# Grove_-_LoRa_Radio_433MHz_v1_0.net
KiCad netlist of a schematic drawn in EAGLE
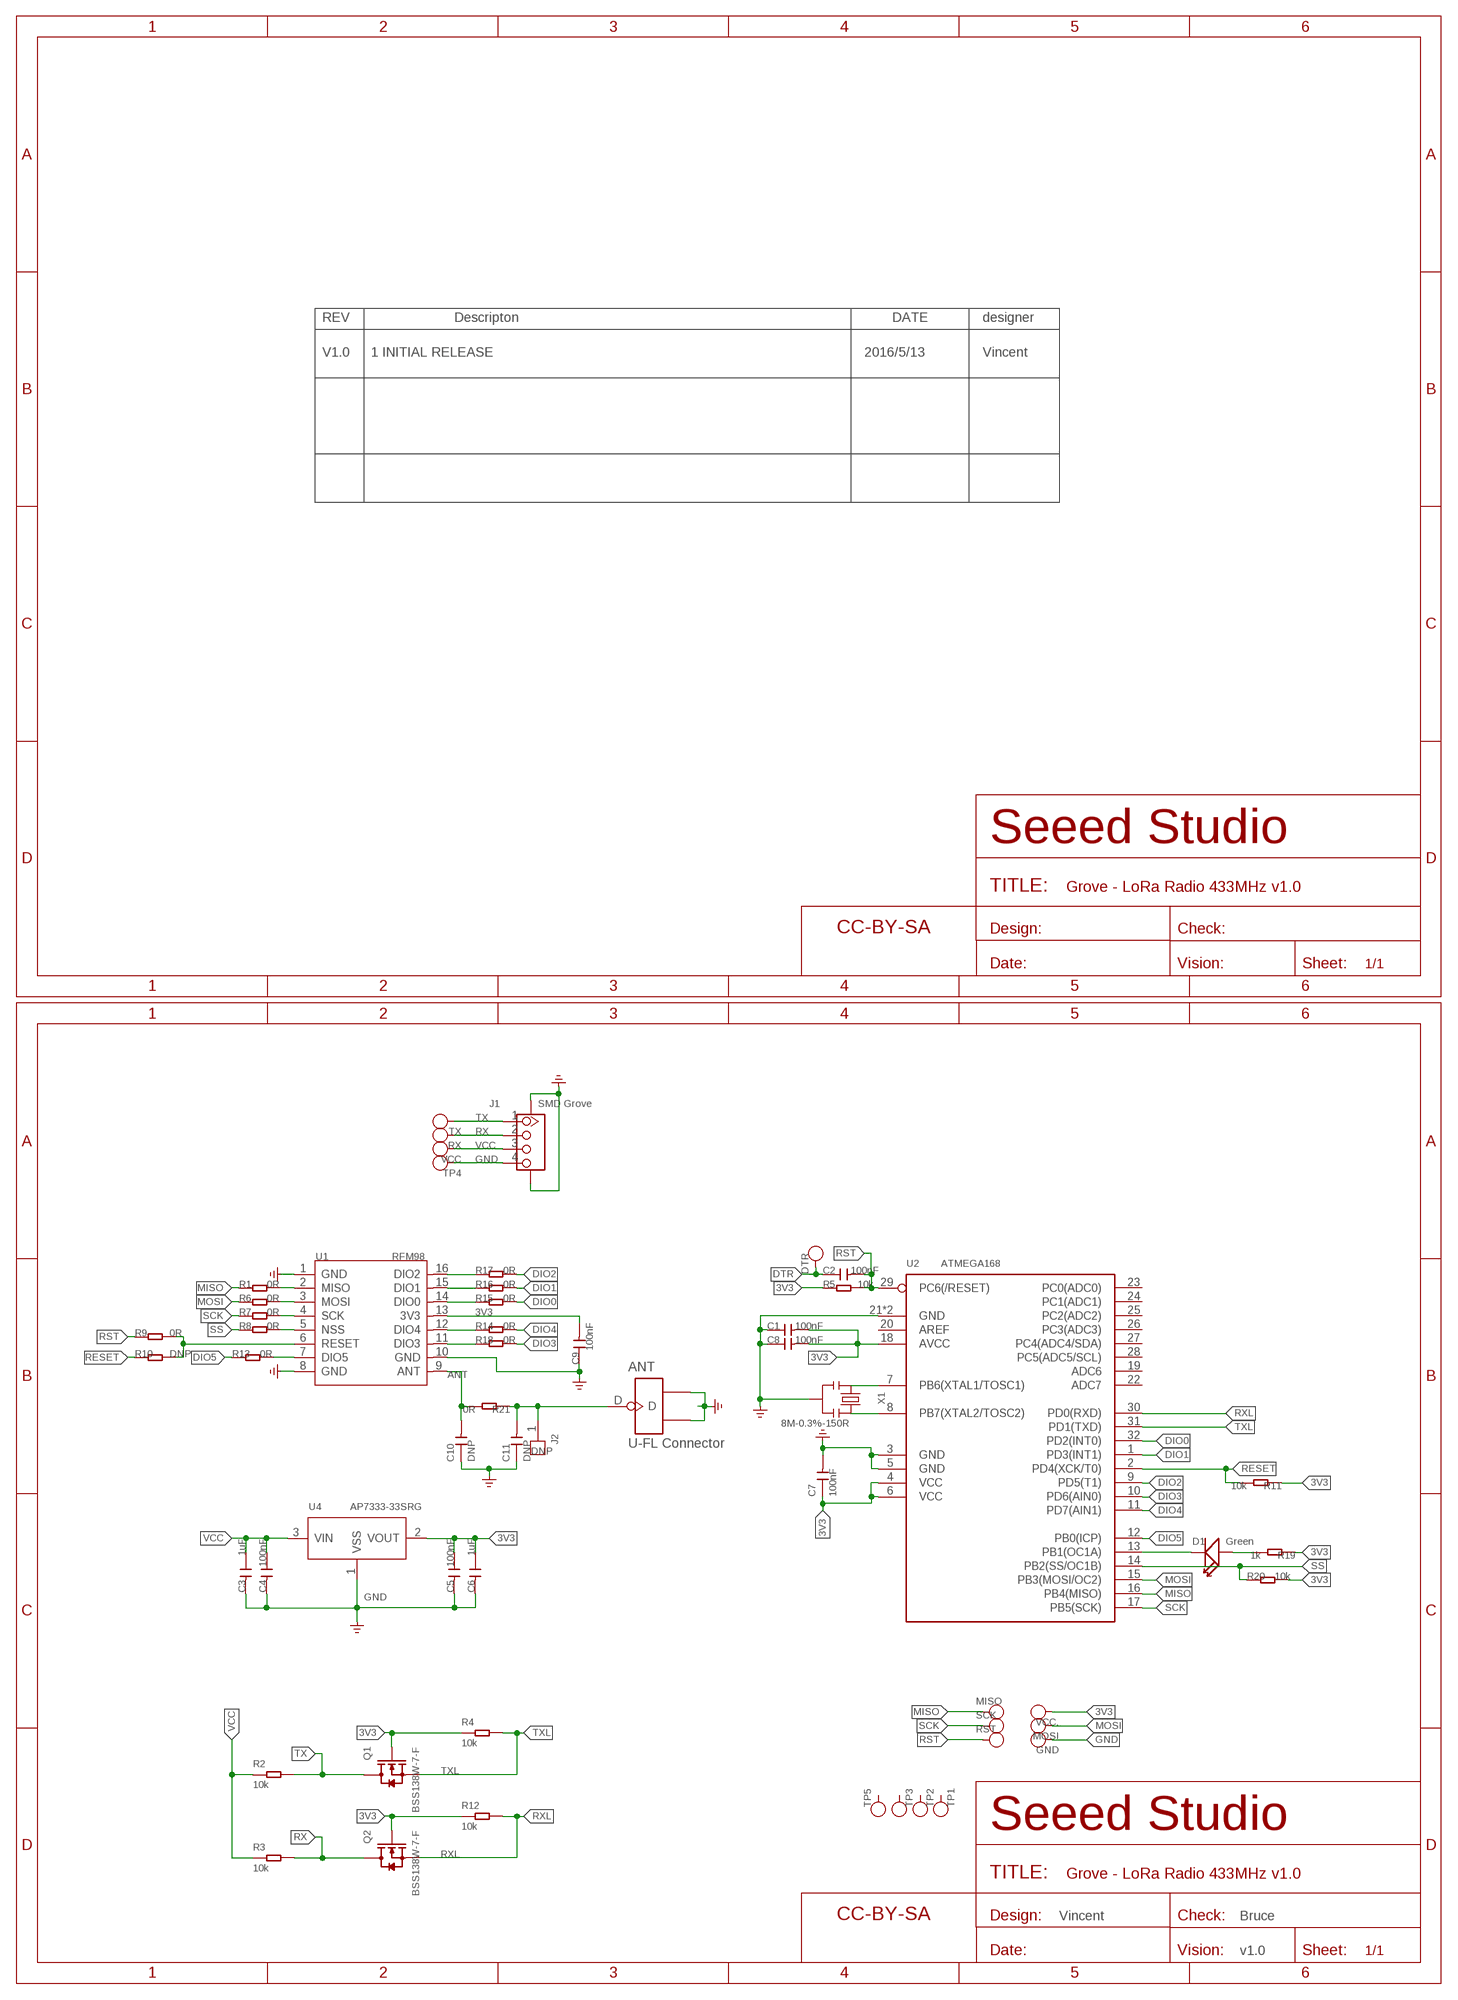
[diagram p0: schematic, sheet 1]

(export (version "E")
  (design (tool "Eeschema 10.0.6"))
  (components
    (comp (ref "ANT")
      (value "U-FL Connector")
      (footprint "eagle-import:U-FL3P-SMD-2.6X2.6X1.0MM")
      (libsource (lib "eagle-import") (part "ANTENNA-U-FL"))
    )
    (comp (ref "C1")
      (value "100nF")
      (footprint "eagle-import:C0402")
      (libsource (lib "eagle-import") (part "CAP-0402"))
    )
    (comp (ref "C2")
      (value "100nF")
      (footprint "eagle-import:C0402")
      (libsource (lib "eagle-import") (part "CAP-0402"))
    )
    (comp (ref "C3")
      (value "1uF")
      (footprint "eagle-import:C0402")
      (libsource (lib "eagle-import") (part "CAP-0402"))
    )
    (comp (ref "C4")
      (value "100nF")
      (footprint "eagle-import:C0402")
      (libsource (lib "eagle-import") (part "CAP-0402"))
    )
    (comp (ref "C5")
      (value "100nF")
      (footprint "eagle-import:C0402")
      (libsource (lib "eagle-import") (part "CAP-0402"))
    )
    (comp (ref "C6")
      (value "1uF")
      (footprint "eagle-import:C0402")
      (libsource (lib "eagle-import") (part "CAP-0402"))
    )
    (comp (ref "C7")
      (value "100nF")
      (footprint "eagle-import:C0402")
      (libsource (lib "eagle-import") (part "CAP-0402"))
    )
    (comp (ref "C8")
      (value "100nF")
      (footprint "eagle-import:C0402")
      (libsource (lib "eagle-import") (part "CAP-0402"))
    )
    (comp (ref "C9")
      (value "100nF")
      (footprint "eagle-import:C0402")
      (libsource (lib "eagle-import") (part "CAP-0402"))
    )
    (comp (ref "C10")
      (value "DNP")
      (footprint "eagle-import:C0402")
      (libsource (lib "eagle-import") (part "CAP-0402"))
    )
    (comp (ref "C11")
      (value "DNP")
      (footprint "eagle-import:C0402")
      (libsource (lib "eagle-import") (part "CAP-0402"))
    )
    (comp (ref "D1")
      (value "Green")
      (footprint "eagle-import:LED-0402")
      (libsource (lib "eagle-import") (part "LED-0402"))
    )
    (comp (ref "DTR")
      (value "TEST-POINT'4545'")
      (footprint "eagle-import:TP-D45MIL")
      (fields (field (name "PARTNO") "DNP"))
      (libsource (lib "eagle-import") (part "TEST-POINT'4545'"))
    )
    (comp (ref "FR1")
      (value "SEEEDSTUDIO-OPEN-SCH-FRAME")
      (footprint "eagle-import:SEEEDSTUDIO-PCB-FRAME")
      (libsource (lib "eagle-import") (part "SEEEDSTUDIO-OPEN-SCH-FRAME"))
    )
    (comp (ref "FR2")
      (value "SEEEDSTUDIO-OPEN-SCH-FRAME")
      (footprint "eagle-import:SEEEDSTUDIO-PCB-FRAME")
      (libsource (lib "eagle-import") (part "SEEEDSTUDIO-OPEN-SCH-FRAME"))
    )
    (comp (ref "GND")
      (value "DNP")
      (footprint "eagle-import:TP-D45MIL")
      (libsource (lib "eagle-import") (part "PAD-TEST-POINT'4545'"))
    )
    (comp (ref "J1")
      (value "SMD Grove")
      (footprint "eagle-import:HW4-SMD-2.0")
      (libsource (lib "eagle-import") (part "GROVE-CONNECTOR-SMD'DD'"))
    )
    (comp (ref "J2")
      (value "DNP")
      (footprint "eagle-import:1P-65_35MIL")
      (libsource (lib "eagle-import") (part "HEADER-1P-35"))
    )
    (comp (ref "MISO")
      (value "DNP")
      (footprint "eagle-import:TP-D45MIL")
      (libsource (lib "eagle-import") (part "PAD-TEST-POINT'4545'"))
    )
    (comp (ref "MOSI")
      (value "DNP")
      (footprint "eagle-import:TP-D45MIL")
      (libsource (lib "eagle-import") (part "PAD-TEST-POINT'4545'"))
    )
    (comp (ref "Q1")
      (value "BSS138W-7-F")
      (footprint "eagle-import:SOT-323")
      (libsource (lib "eagle-import") (part "MOSFET-N'SI1304BDL'"))
    )
    (comp (ref "Q2")
      (value "BSS138W-7-F")
      (footprint "eagle-import:SOT-323")
      (libsource (lib "eagle-import") (part "MOSFET-N'SI1304BDL'"))
    )
    (comp (ref "R1")
      (value "0R")
      (footprint "eagle-import:R0402")
      (libsource (lib "eagle-import") (part "RES-0402"))
    )
    (comp (ref "R2")
      (value "10k")
      (footprint "eagle-import:R0402")
      (libsource (lib "eagle-import") (part "RES-0402"))
    )
    (comp (ref "R3")
      (value "10k")
      (footprint "eagle-import:R0402")
      (libsource (lib "eagle-import") (part "RES-0402"))
    )
    (comp (ref "R4")
      (value "10k")
      (footprint "eagle-import:R0402")
      (libsource (lib "eagle-import") (part "RES-0402"))
    )
    (comp (ref "R5")
      (value "10k")
      (footprint "eagle-import:R0402")
      (libsource (lib "eagle-import") (part "RES-0402"))
    )
    (comp (ref "R6")
      (value "0R")
      (footprint "eagle-import:R0402")
      (libsource (lib "eagle-import") (part "RES-0402"))
    )
    (comp (ref "R7")
      (value "0R")
      (footprint "eagle-import:R0402")
      (libsource (lib "eagle-import") (part "RES-0402"))
    )
    (comp (ref "R8")
      (value "0R")
      (footprint "eagle-import:R0402")
      (libsource (lib "eagle-import") (part "RES-0402"))
    )
    (comp (ref "R9")
      (value "0R")
      (footprint "eagle-import:R0402")
      (libsource (lib "eagle-import") (part "RES-0402"))
    )
    (comp (ref "R10")
      (value "DNP")
      (footprint "eagle-import:R0402")
      (libsource (lib "eagle-import") (part "RES-0402"))
    )
    (comp (ref "R11")
      (value "10k")
      (footprint "eagle-import:R0402")
      (libsource (lib "eagle-import") (part "RES-0402"))
    )
    (comp (ref "R12")
      (value "10k")
      (footprint "eagle-import:R0402")
      (libsource (lib "eagle-import") (part "RES-0402"))
    )
    (comp (ref "R13")
      (value "0R")
      (footprint "eagle-import:R0402")
      (libsource (lib "eagle-import") (part "RES-0402"))
    )
    (comp (ref "R14")
      (value "0R")
      (footprint "eagle-import:R0402")
      (libsource (lib "eagle-import") (part "RES-0402"))
    )
    (comp (ref "R15")
      (value "0R")
      (footprint "eagle-import:R0402")
      (libsource (lib "eagle-import") (part "RES-0402"))
    )
    (comp (ref "R16")
      (value "0R")
      (footprint "eagle-import:R0402")
      (libsource (lib "eagle-import") (part "RES-0402"))
    )
    (comp (ref "R17")
      (value "0R")
      (footprint "eagle-import:R0402")
      (libsource (lib "eagle-import") (part "RES-0402"))
    )
    (comp (ref "R18")
      (value "0R")
      (footprint "eagle-import:R0402")
      (libsource (lib "eagle-import") (part "RES-0402"))
    )
    (comp (ref "R19")
      (value "1k")
      (footprint "eagle-import:R0402")
      (libsource (lib "eagle-import") (part "RES-0402"))
    )
    (comp (ref "R20")
      (value "10k")
      (footprint "eagle-import:R0402")
      (libsource (lib "eagle-import") (part "RES-0402"))
    )
    (comp (ref "R21")
      (value "0R")
      (footprint "eagle-import:R0603")
      (libsource (lib "eagle-import") (part "R-0603"))
    )
    (comp (ref "RST")
      (value "DNP")
      (footprint "eagle-import:TP-D45MIL")
      (libsource (lib "eagle-import") (part "PAD-TEST-POINT'4545'"))
    )
    (comp (ref "RX")
      (value "TEST-POINT'4545'")
      (footprint "eagle-import:TP-D45MIL")
      (fields (field (name "PARTNO") "DNP"))
      (libsource (lib "eagle-import") (part "TEST-POINT'4545'"))
    )
    (comp (ref "SCK")
      (value "DNP")
      (footprint "eagle-import:TP-D45MIL")
      (libsource (lib "eagle-import") (part "PAD-TEST-POINT'4545'"))
    )
    (comp (ref "TP1")
      (value "TEST-POINT'4545'")
      (footprint "eagle-import:TP-D45MIL")
      (fields (field (name "PARTNO") "DNP"))
      (libsource (lib "eagle-import") (part "TEST-POINT'4545'"))
    )
    (comp (ref "TP2")
      (value "TEST-POINT'4545'")
      (footprint "eagle-import:TP-D45MIL")
      (fields (field (name "PARTNO") "DNP"))
      (libsource (lib "eagle-import") (part "TEST-POINT'4545'"))
    )
    (comp (ref "TP3")
      (value "TEST-POINT'4545'")
      (footprint "eagle-import:TP-D45MIL")
      (fields (field (name "PARTNO") "DNP"))
      (libsource (lib "eagle-import") (part "TEST-POINT'4545'"))
    )
    (comp (ref "TP4")
      (value "TEST-POINT'4545'")
      (footprint "eagle-import:TP-D45MIL")
      (fields (field (name "PARTNO") "DNP"))
      (libsource (lib "eagle-import") (part "TEST-POINT'4545'"))
    )
    (comp (ref "TP5")
      (value "TEST-POINT'4545'")
      (footprint "eagle-import:TP-D45MIL")
      (fields (field (name "PARTNO") "DNP"))
      (libsource (lib "eagle-import") (part "TEST-POINT'4545'"))
    )
    (comp (ref "TX")
      (value "TEST-POINT'4545'")
      (footprint "eagle-import:TP-D45MIL")
      (fields (field (name "PARTNO") "DNP"))
      (libsource (lib "eagle-import") (part "TEST-POINT'4545'"))
    )
    (comp (ref "U1")
      (value "RFM98")
      (footprint "eagle-import:MODEM16-2-16X16X1.8MM")
      (libsource (lib "eagle-import") (part "MOUDLE-MODEM-RFM95/96/97/98"))
    )
    (comp (ref "U2")
      (value "ATMEGA168")
      (footprint "eagle-import:QFN32G-0.5-5X5MM")
      (libsource (lib "eagle-import") (part "MCU-ATMEGA8/168/328MU"))
    )
    (comp (ref "U4")
      (value "AP7333-33SRG")
      (footprint "eagle-import:SOT-23")
      (libsource (lib "eagle-import") (part "PMIC-XC6206PMR"))
    )
    (comp (ref "VCC")
      (value "TEST-POINT'4545'")
      (footprint "eagle-import:TP-D45MIL")
      (fields (field (name "PARTNO") "DNP"))
      (libsource (lib "eagle-import") (part "TEST-POINT'4545'"))
    )
    (comp (ref "VCC.")
      (value "NC")
      (footprint "eagle-import:TP-D45MIL")
      (fields (field (name "PARTNO") "DNP"))
      (libsource (lib "eagle-import") (part "PAD-TEST-POINT'4545'"))
    )
    (comp (ref "X1")
      (value "8M-0.3%-150R")
      (footprint "eagle-import:RESONATOR3-SMD-3.6X1.3X0.8MM")
      (libsource (lib "eagle-import") (part "CRYSTAL-RESONATOR'SMD'"))
    )
  )
  (nets
    (net (code "1") (name "/ANT") (class "Default")
      (node (ref "C10") (pin "2") (pinfunction "2_2") (pintype "passive"))
      (node (ref "R21") (pin "2") (pinfunction "2_2") (pintype "passive"))
      (node (ref "U1") (pin "9") (pinfunction "ANT_9") (pintype "bidirectional"))
    )
    (net (code "2") (name "3V3") (class "Default")
      (node (ref "C1") (pin "2") (pinfunction "2_2") (pintype "passive"))
      (node (ref "C5") (pin "1") (pinfunction "1_1") (pintype "passive"))
      (node (ref "C6") (pin "1") (pinfunction "1_1") (pintype "passive"))
      (node (ref "C7") (pin "1") (pinfunction "1_1") (pintype "passive"))
      (node (ref "C8") (pin "2") (pinfunction "2_2") (pintype "passive"))
      (node (ref "C9") (pin "2") (pinfunction "2_2") (pintype "passive"))
      (node (ref "Q1") (pin "1") (pinfunction "G_1") (pintype "passive"))
      (node (ref "Q2") (pin "1") (pinfunction "G_1") (pintype "passive"))
      (node (ref "R11") (pin "2") (pinfunction "2_2") (pintype "passive"))
      (node (ref "R12") (pin "1") (pinfunction "1_1") (pintype "passive"))
      (node (ref "R19") (pin "2") (pinfunction "2_2") (pintype "passive"))
      (node (ref "R20") (pin "2") (pinfunction "2_2") (pintype "passive"))
      (node (ref "R4") (pin "1") (pinfunction "1_1") (pintype "passive"))
      (node (ref "R5") (pin "2") (pinfunction "2_2") (pintype "passive"))
      (node (ref "U1") (pin "13") (pinfunction "3V3_13") (pintype "bidirectional"))
      (node (ref "U2") (pin "18") (pinfunction "AVCC_18") (pintype "bidirectional"))
      (node (ref "U2") (pin "4") (pinfunction "VCC_4") (pintype "bidirectional"))
      (node (ref "U2") (pin "6") (pinfunction "VCC_6") (pintype "bidirectional"))
      (node (ref "U4") (pin "2") (pinfunction "VOUT_2") (pintype "bidirectional"))
      (node (ref "VCC.") (pin "T") (pinfunction "T_T") (pintype "bidirectional"))
    )
    (net (code "3") (name "DIO0") (class "Default")
      (node (ref "R15") (pin "2") (pinfunction "2_2") (pintype "passive"))
      (node (ref "U2") (pin "32") (pinfunction "PD2(INT0)_32") (pintype "bidirectional"))
    )
    (net (code "4") (name "DIO1") (class "Default")
      (node (ref "R16") (pin "2") (pinfunction "2_2") (pintype "passive"))
      (node (ref "U2") (pin "1") (pinfunction "PD3(INT1)_1") (pintype "bidirectional"))
    )
    (net (code "5") (name "DIO2") (class "Default")
      (node (ref "R17") (pin "2") (pinfunction "2_2") (pintype "passive"))
      (node (ref "U2") (pin "9") (pinfunction "PD5(T1)_9") (pintype "bidirectional"))
    )
    (net (code "6") (name "DIO3") (class "Default")
      (node (ref "R18") (pin "2") (pinfunction "2_2") (pintype "passive"))
      (node (ref "U2") (pin "10") (pinfunction "PD6(AIN0)_10") (pintype "bidirectional"))
    )
    (net (code "7") (name "DIO4") (class "Default")
      (node (ref "R14") (pin "2") (pinfunction "2_2") (pintype "passive"))
      (node (ref "U2") (pin "11") (pinfunction "PD7(AIN1)_11") (pintype "bidirectional"))
    )
    (net (code "8") (name "DIO5") (class "Default")
      (node (ref "R13") (pin "1") (pinfunction "1_1") (pintype "passive"))
      (node (ref "U2") (pin "12") (pinfunction "PB0(ICP)_12") (pintype "bidirectional"))
    )
    (net (code "9") (name "DTR") (class "Default")
      (node (ref "C2") (pin "1") (pinfunction "1_1") (pintype "passive"))
      (node (ref "DTR") (pin "T") (pinfunction "T_T") (pintype "bidirectional"))
    )
    (net (code "10") (name "GND") (class "Default")
      (node (ref "ANT") (pin "GND1") (pinfunction "GND1_GND1") (pintype "bidirectional"))
      (node (ref "ANT") (pin "GND2") (pinfunction "GND2_GND2") (pintype "bidirectional"))
      (node (ref "C1") (pin "1") (pinfunction "1_1") (pintype "passive"))
      (node (ref "C10") (pin "1") (pinfunction "1_1") (pintype "passive"))
      (node (ref "C11") (pin "1") (pinfunction "1_1") (pintype "passive"))
      (node (ref "C3") (pin "2") (pinfunction "2_2") (pintype "passive"))
      (node (ref "C4") (pin "2") (pinfunction "2_2") (pintype "passive"))
      (node (ref "C5") (pin "2") (pinfunction "2_2") (pintype "passive"))
      (node (ref "C6") (pin "2") (pinfunction "2_2") (pintype "passive"))
      (node (ref "C7") (pin "2") (pinfunction "2_2") (pintype "passive"))
      (node (ref "C8") (pin "1") (pinfunction "1_1") (pintype "passive"))
      (node (ref "C9") (pin "1") (pinfunction "1_1") (pintype "passive"))
      (node (ref "GND") (pin "T") (pinfunction "T_T") (pintype "bidirectional"))
      (node (ref "J1") (pin "4") (pinfunction "4_4") (pintype "bidirectional"))
      (node (ref "J1") (pin "SS1") (pinfunction "SS1_SS1") (pintype "bidirectional"))
      (node (ref "J1") (pin "SS2") (pinfunction "SS2_SS2") (pintype "bidirectional"))
      (node (ref "TP4") (pin "T") (pinfunction "T_T") (pintype "bidirectional"))
      (node (ref "U1") (pin "1") (pinfunction "GND_1") (pintype "bidirectional"))
      (node (ref "U1") (pin "10") (pinfunction "GND_10") (pintype "bidirectional"))
      (node (ref "U1") (pin "8") (pinfunction "GND_8") (pintype "bidirectional"))
      (node (ref "U2") (pin "21") (pinfunction "GND_21") (pintype "bidirectional"))
      (node (ref "U2") (pin "3") (pinfunction "GND_3") (pintype "bidirectional"))
      (node (ref "U2") (pin "33") (pinfunction "GND_33") (pintype "bidirectional"))
      (node (ref "U2") (pin "5") (pinfunction "GND_5") (pintype "bidirectional"))
      (node (ref "U4") (pin "1") (pinfunction "VSS_1") (pintype "bidirectional"))
      (node (ref "X1") (pin "2") (pinfunction "2_2") (pintype "passive"))
    )
    (net (code "11") (name "MISO") (class "Default")
      (node (ref "MISO") (pin "T") (pinfunction "T_T") (pintype "bidirectional"))
      (node (ref "R1") (pin "1") (pinfunction "1_1") (pintype "passive"))
      (node (ref "U2") (pin "16") (pinfunction "PB4(MISO)_16") (pintype "bidirectional"))
    )
    (net (code "12") (name "MOSI") (class "Default")
      (node (ref "MOSI") (pin "T") (pinfunction "T_T") (pintype "bidirectional"))
      (node (ref "R6") (pin "1") (pinfunction "1_1") (pintype "passive"))
      (node (ref "U2") (pin "15") (pinfunction "PB3(MOSI/OC2)_15") (pintype "bidirectional"))
    )
    (net (code "13") (name "Net-(ANT-PadD)") (class "Default")
      (node (ref "ANT") (pin "D") (pinfunction "D_D") (pintype "bidirectional"))
      (node (ref "C11") (pin "2") (pinfunction "2_2") (pintype "passive"))
      (node (ref "J2") (pin "1") (pinfunction "1_1") (pintype "bidirectional"))
      (node (ref "R21") (pin "1") (pinfunction "1_1") (pintype "passive"))
    )
    (net (code "14") (name "Net-(D1-Pad+)") (class "Default")
      (node (ref "D1") (pin "+") (pinfunction "+_+") (pintype "passive"))
      (node (ref "R19") (pin "1") (pinfunction "1_1") (pintype "passive"))
    )
    (net (code "15") (name "Net-(U1-DIO0)") (class "Default")
      (node (ref "R15") (pin "1") (pinfunction "1_1") (pintype "passive"))
      (node (ref "U1") (pin "14") (pinfunction "DIO0_14") (pintype "bidirectional"))
    )
    (net (code "16") (name "Net-(U1-DIO1)") (class "Default")
      (node (ref "R16") (pin "1") (pinfunction "1_1") (pintype "passive"))
      (node (ref "U1") (pin "15") (pinfunction "DIO1_15") (pintype "bidirectional"))
    )
    (net (code "17") (name "Net-(U1-DIO2)") (class "Default")
      (node (ref "R17") (pin "1") (pinfunction "1_1") (pintype "passive"))
      (node (ref "U1") (pin "16") (pinfunction "DIO2_16") (pintype "bidirectional"))
    )
    (net (code "18") (name "Net-(U1-DIO3)") (class "Default")
      (node (ref "R18") (pin "1") (pinfunction "1_1") (pintype "passive"))
      (node (ref "U1") (pin "11") (pinfunction "DIO3_11") (pintype "bidirectional"))
    )
    (net (code "19") (name "Net-(U1-DIO4)") (class "Default")
      (node (ref "R14") (pin "1") (pinfunction "1_1") (pintype "passive"))
      (node (ref "U1") (pin "12") (pinfunction "DIO4_12") (pintype "bidirectional"))
    )
    (net (code "20") (name "Net-(U1-DIO5)") (class "Default")
      (node (ref "R13") (pin "2") (pinfunction "2_2") (pintype "passive"))
      (node (ref "U1") (pin "7") (pinfunction "DIO5_7") (pintype "bidirectional"))
    )
    (net (code "21") (name "Net-(U1-MISO)") (class "Default")
      (node (ref "R1") (pin "2") (pinfunction "2_2") (pintype "passive"))
      (node (ref "U1") (pin "2") (pinfunction "MISO_2") (pintype "bidirectional"))
    )
    (net (code "22") (name "Net-(U1-MOSI)") (class "Default")
      (node (ref "R6") (pin "2") (pinfunction "2_2") (pintype "passive"))
      (node (ref "U1") (pin "3") (pinfunction "MOSI_3") (pintype "bidirectional"))
    )
    (net (code "23") (name "Net-(U1-NSS)") (class "Default")
      (node (ref "R8") (pin "2") (pinfunction "2_2") (pintype "passive"))
      (node (ref "U1") (pin "5") (pinfunction "NSS_5") (pintype "bidirectional"))
    )
    (net (code "24") (name "Net-(U1-RESET)") (class "Default")
      (node (ref "R10") (pin "1") (pinfunction "1_1") (pintype "passive"))
      (node (ref "R9") (pin "1") (pinfunction "1_1") (pintype "passive"))
      (node (ref "U1") (pin "6") (pinfunction "RESET_6") (pintype "bidirectional"))
    )
    (net (code "25") (name "Net-(U1-SCK)") (class "Default")
      (node (ref "R7") (pin "2") (pinfunction "2_2") (pintype "passive"))
      (node (ref "U1") (pin "4") (pinfunction "SCK_4") (pintype "bidirectional"))
    )
    (net (code "26") (name "Net-(U2-PB1(OC1A))") (class "Default")
      (node (ref "D1") (pin "-") (pinfunction "-_-") (pintype "passive"))
      (node (ref "U2") (pin "13") (pinfunction "PB1(OC1A)_13") (pintype "bidirectional"))
    )
    (net (code "27") (name "Net-(U2-PB6(XTAL1{slash}TOSC1))") (class "Default")
      (node (ref "U2") (pin "7") (pinfunction "PB6(XTAL1/TOSC1)_7") (pintype "bidirectional"))
      (node (ref "X1") (pin "1") (pinfunction "1_1") (pintype "passive"))
    )
    (net (code "28") (name "Net-(U2-PB7(XTAL2{slash}TOSC2))") (class "Default")
      (node (ref "U2") (pin "8") (pinfunction "PB7(XTAL2/TOSC2)_8") (pintype "bidirectional"))
      (node (ref "X1") (pin "3") (pinfunction "3_3") (pintype "passive"))
    )
    (net (code "29") (name "RESET") (class "Default")
      (node (ref "R10") (pin "2") (pinfunction "2_2") (pintype "passive"))
      (node (ref "R11") (pin "1") (pinfunction "1_1") (pintype "passive"))
      (node (ref "U2") (pin "2") (pinfunction "PD4(XCK/T0)_2") (pintype "bidirectional"))
    )
    (net (code "30") (name "RST") (class "Default")
      (node (ref "C2") (pin "2") (pinfunction "2_2") (pintype "passive"))
      (node (ref "R5") (pin "1") (pinfunction "1_1") (pintype "passive"))
      (node (ref "R9") (pin "2") (pinfunction "2_2") (pintype "passive"))
      (node (ref "RST") (pin "T") (pinfunction "T_T") (pintype "bidirectional"))
      (node (ref "U2") (pin "29") (pinfunction "PC6(/RESET)_29") (pintype "bidirectional"))
    )
    (net (code "31") (name "RX") (class "Default")
      (node (ref "J1") (pin "2") (pinfunction "2_2") (pintype "bidirectional"))
      (node (ref "Q2") (pin "3") (pinfunction "D_3") (pintype "passive"))
      (node (ref "R3") (pin "2") (pinfunction "2_2") (pintype "passive"))
      (node (ref "RX") (pin "T") (pinfunction "T_T") (pintype "bidirectional"))
    )
    (net (code "32") (name "RXL") (class "Default")
      (node (ref "Q2") (pin "2") (pinfunction "S_2") (pintype "passive"))
      (node (ref "R12") (pin "2") (pinfunction "2_2") (pintype "passive"))
      (node (ref "U2") (pin "30") (pinfunction "PD0(RXD)_30") (pintype "bidirectional"))
    )
    (net (code "33") (name "SCK") (class "Default")
      (node (ref "R7") (pin "1") (pinfunction "1_1") (pintype "passive"))
      (node (ref "SCK") (pin "T") (pinfunction "T_T") (pintype "bidirectional"))
      (node (ref "U2") (pin "17") (pinfunction "PB5(SCK)_17") (pintype "bidirectional"))
    )
    (net (code "34") (name "SS") (class "Default")
      (node (ref "R20") (pin "1") (pinfunction "1_1") (pintype "passive"))
      (node (ref "R8") (pin "1") (pinfunction "1_1") (pintype "passive"))
      (node (ref "U2") (pin "14") (pinfunction "PB2(SS/OC1B)_14") (pintype "bidirectional"))
    )
    (net (code "35") (name "TX") (class "Default")
      (node (ref "J1") (pin "1") (pinfunction "1_1") (pintype "bidirectional"))
      (node (ref "Q1") (pin "3") (pinfunction "D_3") (pintype "passive"))
      (node (ref "R2") (pin "2") (pinfunction "2_2") (pintype "passive"))
      (node (ref "TX") (pin "T") (pinfunction "T_T") (pintype "bidirectional"))
    )
    (net (code "36") (name "TXL") (class "Default")
      (node (ref "Q1") (pin "2") (pinfunction "S_2") (pintype "passive"))
      (node (ref "R4") (pin "2") (pinfunction "2_2") (pintype "passive"))
      (node (ref "U2") (pin "31") (pinfunction "PD1(TXD)_31") (pintype "bidirectional"))
    )
    (net (code "37") (name "VCC") (class "Default")
      (node (ref "C3") (pin "1") (pinfunction "1_1") (pintype "passive"))
      (node (ref "C4") (pin "1") (pinfunction "1_1") (pintype "passive"))
      (node (ref "J1") (pin "3") (pinfunction "3_3") (pintype "bidirectional"))
      (node (ref "R2") (pin "1") (pinfunction "1_1") (pintype "passive"))
      (node (ref "R3") (pin "1") (pinfunction "1_1") (pintype "passive"))
      (node (ref "U4") (pin "3") (pinfunction "VIN_3") (pintype "bidirectional"))
      (node (ref "VCC") (pin "T") (pinfunction "T_T") (pintype "bidirectional"))
    )
    (net (code "38") (name "unconnected-(TP1-PadT)") (class "Default")
      (node (ref "TP1") (pin "T") (pinfunction "T_T") (pintype "bidirectional"))
    )
    (net (code "39") (name "unconnected-(TP2-PadT)") (class "Default")
      (node (ref "TP2") (pin "T") (pinfunction "T_T") (pintype "bidirectional"))
    )
    (net (code "40") (name "unconnected-(TP3-PadT)") (class "Default")
      (node (ref "TP3") (pin "T") (pinfunction "T_T") (pintype "bidirectional"))
    )
    (net (code "41") (name "unconnected-(TP5-PadT)") (class "Default")
      (node (ref "TP5") (pin "T") (pinfunction "T_T") (pintype "bidirectional"))
    )
    (net (code "42") (name "unconnected-(U2-ADC6-Pad19)") (class "Default")
      (node (ref "U2") (pin "19") (pinfunction "ADC6_19") (pintype "bidirectional"))
    )
    (net (code "43") (name "unconnected-(U2-ADC7-Pad22)") (class "Default")
      (node (ref "U2") (pin "22") (pinfunction "ADC7_22") (pintype "bidirectional"))
    )
    (net (code "44") (name "unconnected-(U2-AREF-Pad20)") (class "Default")
      (node (ref "U2") (pin "20") (pinfunction "AREF_20") (pintype "bidirectional"))
    )
    (net (code "45") (name "unconnected-(U2-PC0(ADC0)-Pad23)") (class "Default")
      (node (ref "U2") (pin "23") (pinfunction "PC0(ADC0)_23") (pintype "bidirectional"))
    )
    (net (code "46") (name "unconnected-(U2-PC1(ADC1)-Pad24)") (class "Default")
      (node (ref "U2") (pin "24") (pinfunction "PC1(ADC1)_24") (pintype "bidirectional"))
    )
    (net (code "47") (name "unconnected-(U2-PC2(ADC2)-Pad25)") (class "Default")
      (node (ref "U2") (pin "25") (pinfunction "PC2(ADC2)_25") (pintype "bidirectional"))
    )
    (net (code "48") (name "unconnected-(U2-PC3(ADC3)-Pad26)") (class "Default")
      (node (ref "U2") (pin "26") (pinfunction "PC3(ADC3)_26") (pintype "bidirectional"))
    )
    (net (code "49") (name "unconnected-(U2-PC4(ADC4{slash}SDA)-Pad27)") (class "Default")
      (node (ref "U2") (pin "27") (pinfunction "PC4(ADC4/SDA)_27") (pintype "bidirectional"))
    )
    (net (code "50") (name "unconnected-(U2-PC5(ADC5{slash}SCL)-Pad28)") (class "Default")
      (node (ref "U2") (pin "28") (pinfunction "PC5(ADC5/SCL)_28") (pintype "bidirectional"))
    )
  )
)
